# base_tiempo.net
KiCad netlist of a schematic drawn in Altium Designer
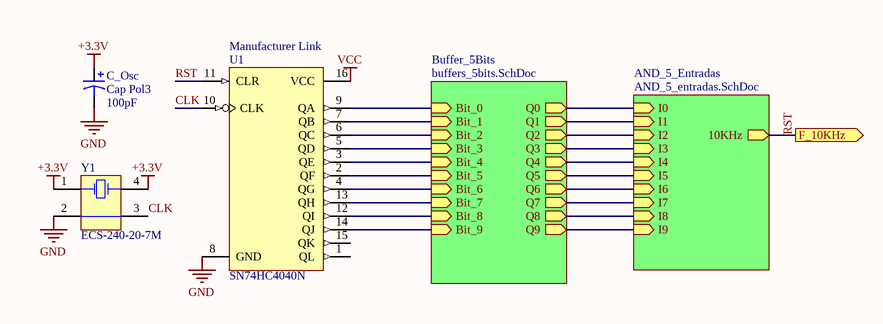
[diagram p0: base_tiempo.SchDoc]

(export (version "E")
  (design (tool "Eeschema 10.0.6"))
  (components
    (comp (ref "C_Osc")
      (value "Cap Pol3")
      (footprint "C0805")
      (description "Polarized Capacitor (Surface Mount)")
      (fields (field (name "ALTIUM_VALUE") "100pF") (field (name "PUBLISHER") "Altium Limited"))
      (libsource (lib "Miscellaneous Devices") (part "Cap Pol3"))
    )
    (comp (ref "U1")
      (value "SN74HC4040N")
      (footprint "N016")
      (description "12-Bit Asynchronous Binary Counter")
      (fields
        (field (name "COMPONENTLINK1DESCRIPTION") "Manufacturer Link")
        (field (name "PUBLISHER") "Altium Limited")
      )
      (libsource (lib "TI Logic Counter") (part "SN74HC4040N"))
    )
    (comp (ref "Y1")
      (value "ECS-240-20-7M")
      (footprint "ECX-3M")
      (description "Crystal Oscillator")
      (fields (field (name "PUBLISHER") "Altium Limited"))
      (libsource (lib "ECS Crystal Oscillator") (part "ECS-240-20-7M"))
    )
  )
  (nets
    (net (code "1") (name "+3.3V") (class "Default")
      (node (ref "C_Osc") (pin "1") (pinfunction "1_1") (pintype "passive"))
      (node (ref "Y1") (pin "1") (pinfunction "OSC1_1") (pintype "passive"))
      (node (ref "Y1") (pin "4") (pinfunction "OSC2_4") (pintype "passive"))
    )
    (net (code "2") (name "/Bit_0") (class "Default")
      (node (ref "U1") (pin "9") (pinfunction "QA_9") (pintype "output"))
    )
    (net (code "3") (name "/Bit_1") (class "Default")
      (node (ref "U1") (pin "7") (pinfunction "QB_7") (pintype "output"))
    )
    (net (code "4") (name "/Bit_2") (class "Default")
      (node (ref "U1") (pin "6") (pinfunction "QC_6") (pintype "output"))
    )
    (net (code "5") (name "/Bit_3") (class "Default")
      (node (ref "U1") (pin "5") (pinfunction "QD_5") (pintype "output"))
    )
    (net (code "6") (name "/Bit_4") (class "Default")
      (node (ref "U1") (pin "3") (pinfunction "QE_3") (pintype "output"))
    )
    (net (code "7") (name "/Bit_5") (class "Default")
      (node (ref "U1") (pin "2") (pinfunction "QF_2") (pintype "output"))
    )
    (net (code "8") (name "/Bit_6") (class "Default")
      (node (ref "U1") (pin "4") (pinfunction "QG_4") (pintype "output"))
    )
    (net (code "9") (name "/Bit_7") (class "Default")
      (node (ref "U1") (pin "13") (pinfunction "QH_13") (pintype "output"))
    )
    (net (code "10") (name "/Bit_8") (class "Default")
      (node (ref "U1") (pin "12") (pinfunction "QI_12") (pintype "output"))
    )
    (net (code "11") (name "/Bit_9") (class "Default")
      (node (ref "U1") (pin "14") (pinfunction "QJ_14") (pintype "output"))
    )
    (net (code "12") (name "/CLK") (class "Default")
      (node (ref "U1") (pin "10") (pinfunction "CLK_10") (pintype "input"))
      (node (ref "Y1") (pin "3") (pinfunction "COM_3") (pintype "passive"))
    )
    (net (code "23") (name "/RST") (class "Default")
      (node (ref "U1") (pin "11") (pinfunction "CLR_11") (pintype "input"))
    )
    (net (code "24") (name "GND") (class "Default")
      (node (ref "C_Osc") (pin "2") (pinfunction "2_2") (pintype "passive"))
      (node (ref "U1") (pin "8") (pinfunction "GND_8") (pintype "power_in"))
      (node (ref "Y1") (pin "2") (pinfunction "COM_2") (pintype "passive"))
    )
    (net (code "25") (name "VCC") (class "Default")
      (node (ref "U1") (pin "16") (pinfunction "VCC_16") (pintype "power_in"))
    )
    (net (code "26") (name "unconnected-(U1-QK-Pad15)") (class "Default")
      (node (ref "U1") (pin "15") (pinfunction "QK_15") (pintype "output"))
    )
    (net (code "27") (name "unconnected-(U1-QL-Pad1)") (class "Default")
      (node (ref "U1") (pin "1") (pinfunction "QL_1") (pintype "output"))
    )
  )
)
